# Sheet1.net
KiCad netlist of a schematic drawn in Altium Designer
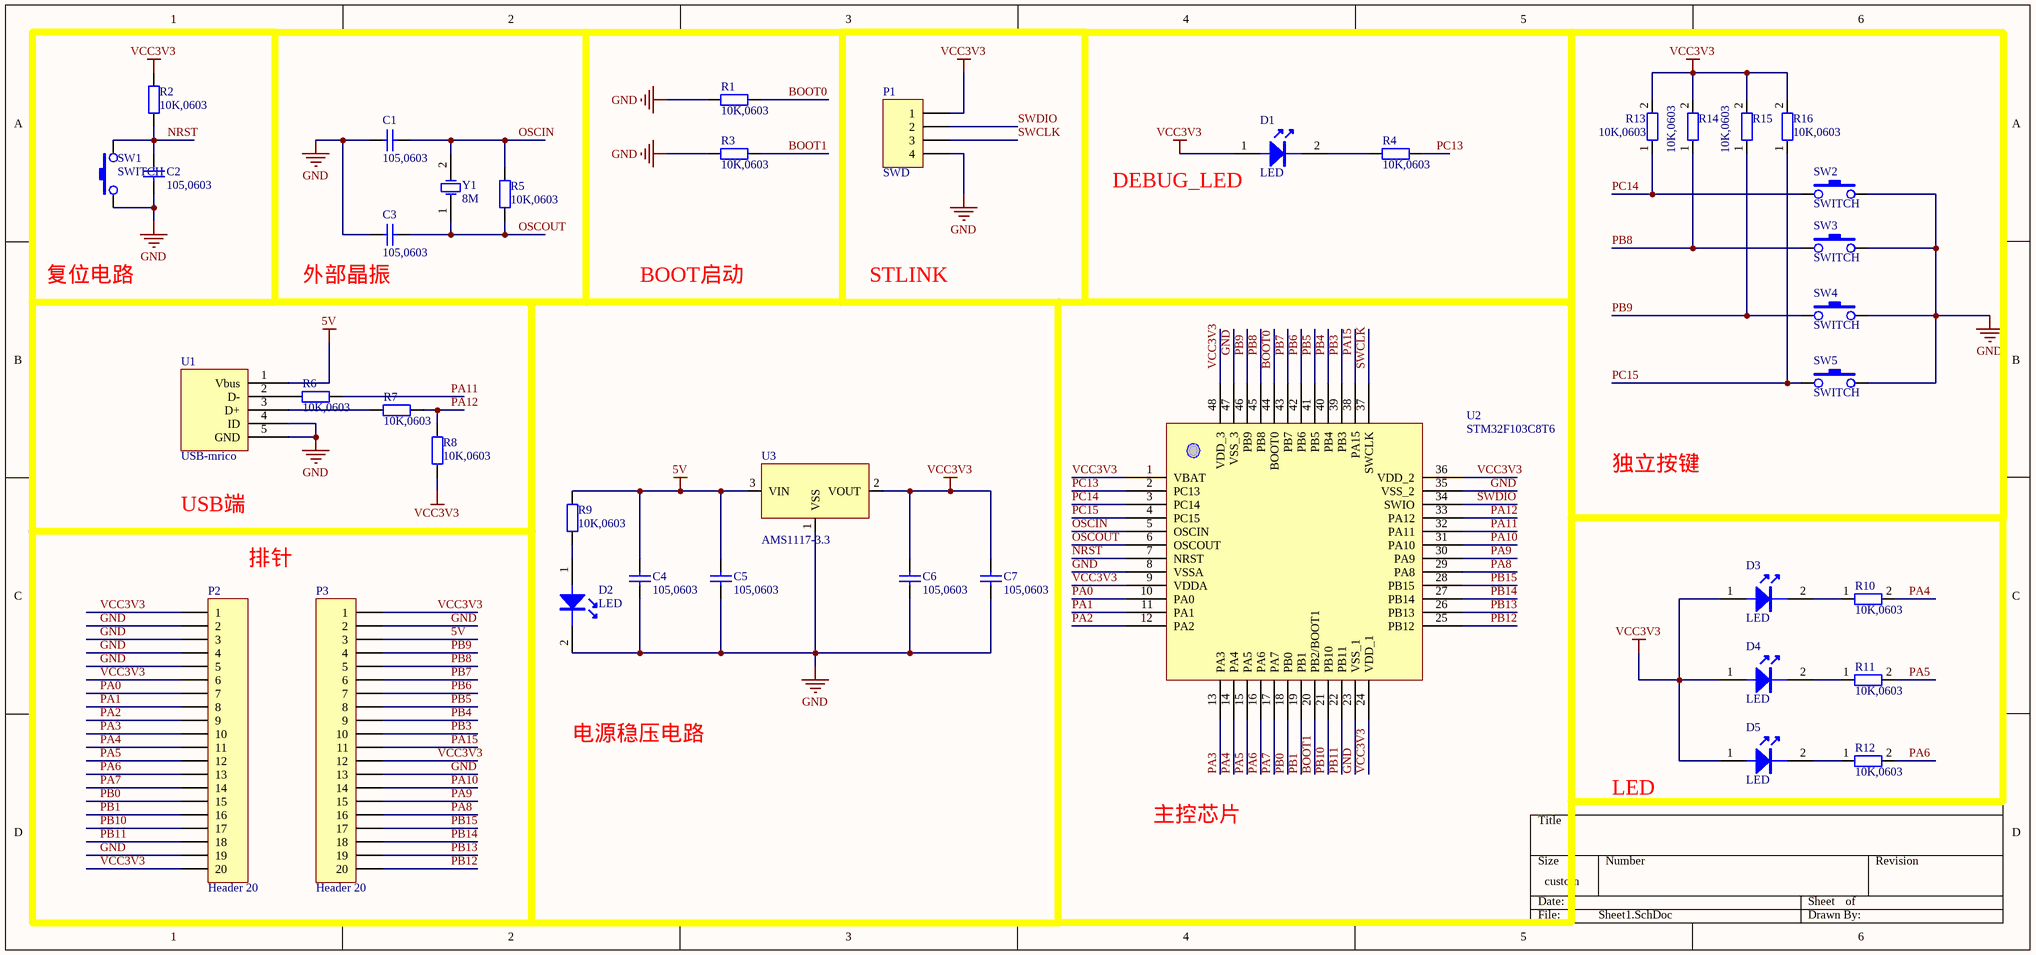
[diagram p0: Sheet1.SchDoc]

(export (version "E")
  (design (tool "Eeschema 10.0.6"))
  (components
    (comp (ref "C1")
      (value "105,0603")
      (footprint "CAP 0603")
      (description "Capacitor")
      (fields (field (name "PUBLISHER") "Altium Limited"))
      (libsource (lib "Schlib1") (part "Cap"))
    )
    (comp (ref "C2")
      (value "105,0603")
      (footprint "CAP 0603")
      (description "Capacitor")
      (fields (field (name "PUBLISHER") "Altium Limited"))
      (libsource (lib "Schlib1") (part "Cap"))
    )
    (comp (ref "C3")
      (value "105,0603")
      (footprint "CAP 0603")
      (description "Capacitor")
      (fields (field (name "PUBLISHER") "Altium Limited"))
      (libsource (lib "Schlib1") (part "Cap"))
    )
    (comp (ref "C4")
      (value "105,0603")
      (footprint "CAP 0603")
      (description "Capacitor")
      (fields (field (name "PUBLISHER") "Altium Limited"))
      (libsource (lib "Schlib1") (part "Cap"))
    )
    (comp (ref "C5")
      (value "105,0603")
      (footprint "CAP 0603")
      (description "Capacitor")
      (fields (field (name "PUBLISHER") "Altium Limited"))
      (libsource (lib "Schlib1") (part "Cap"))
    )
    (comp (ref "C6")
      (value "105,0603")
      (footprint "CAP 0603")
      (description "Capacitor")
      (fields (field (name "PUBLISHER") "Altium Limited"))
      (libsource (lib "Schlib1") (part "Cap"))
    )
    (comp (ref "C7")
      (value "105,0603")
      (footprint "CAP 0603")
      (description "Capacitor")
      (fields (field (name "PUBLISHER") "Altium Limited"))
      (libsource (lib "Schlib1") (part "Cap"))
    )
    (comp (ref "D1") (value "LED") (footprint "LED 0603R") (libsource (lib "Schlib1") (part "LED")))
    (comp (ref "D2") (value "LED") (footprint "LED 0603R") (libsource (lib "Schlib1") (part "LED")))
    (comp (ref "D3") (value "LED") (footprint "LED 0603R") (libsource (lib "Schlib1") (part "LED")))
    (comp (ref "D4") (value "LED") (footprint "LED 0603R") (libsource (lib "Schlib1") (part "LED")))
    (comp (ref "D5") (value "LED") (footprint "LED 0603R") (libsource (lib "Schlib1") (part "LED")))
    (comp (ref "P1")
      (value "SWD")
      (footprint "HDR2.54-WI-4P")
      (description "Header, 4-Pin")
      (fields (field (name "PUBLISHER") "Altium Limited"))
      (libsource (lib "Schlib1") (part "Header 4"))
    )
    (comp (ref "P2")
      (value "Header 20")
      (footprint "HDR2.54-LI-20P")
      (description "Header, 20-Pin")
      (fields (field (name "PUBLISHER") "Altium Limited"))
      (libsource (lib "Schlib1") (part "Header 20"))
    )
    (comp (ref "P3")
      (value "Header 20")
      (footprint "HDR2.54-LI-20P")
      (description "Header, 20-Pin")
      (fields (field (name "PUBLISHER") "Altium Limited"))
      (libsource (lib "") (part "Header 20_1"))
    )
    (comp (ref "R1")
      (value "10K,0603")
      (footprint "RES 0603")
      (description "Resistor")
      (fields (field (name "PUBLISHER") "Altium Limited"))
      (libsource (lib "") (part "Res_1"))
    )
    (comp (ref "R2")
      (value "10K,0603")
      (footprint "RES 0603")
      (description "Resistor")
      (fields (field (name "PUBLISHER") "Altium Limited"))
      (libsource (lib "") (part "Res_2"))
    )
    (comp (ref "R3")
      (value "10K,0603")
      (footprint "RES 0603")
      (description "Resistor")
      (fields (field (name "PUBLISHER") "Altium Limited"))
      (libsource (lib "") (part "Res_1"))
    )
    (comp (ref "R4")
      (value "10K,0603")
      (footprint "RES 0603")
      (description "Resistor")
      (fields (field (name "PUBLISHER") "Altium Limited"))
      (libsource (lib "") (part "Res_1"))
    )
    (comp (ref "R5")
      (value "10K,0603")
      (footprint "RES 0603")
      (description "Resistor")
      (fields (field (name "PUBLISHER") "Altium Limited"))
      (libsource (lib "") (part "Res_2"))
    )
    (comp (ref "R6")
      (value "10K,0603")
      (footprint "RES 0603")
      (description "Resistor")
      (fields (field (name "PUBLISHER") "Altium Limited"))
      (libsource (lib "") (part "Res_1"))
    )
    (comp (ref "R7")
      (value "10K,0603")
      (footprint "RES 0603")
      (description "Resistor")
      (fields (field (name "PUBLISHER") "Altium Limited"))
      (libsource (lib "") (part "Res_1"))
    )
    (comp (ref "R8")
      (value "10K,0603")
      (footprint "RES 0603")
      (description "Resistor")
      (fields (field (name "PUBLISHER") "Altium Limited"))
      (libsource (lib "") (part "Res_2"))
    )
    (comp (ref "R9")
      (value "10K,0603")
      (footprint "RES 0603")
      (description "Resistor")
      (fields (field (name "PUBLISHER") "Altium Limited"))
      (libsource (lib "") (part "Res_2"))
    )
    (comp (ref "R10")
      (value "10K,0603")
      (footprint "RES 0603")
      (description "Resistor")
      (fields (field (name "PUBLISHER") "Altium Limited"))
      (libsource (lib "Schlib1") (part "Res"))
    )
    (comp (ref "R11")
      (value "10K,0603")
      (footprint "RES 0603")
      (description "Resistor")
      (fields (field (name "PUBLISHER") "Altium Limited"))
      (libsource (lib "Schlib1") (part "Res"))
    )
    (comp (ref "R12")
      (value "10K,0603")
      (footprint "RES 0603")
      (description "Resistor")
      (fields (field (name "PUBLISHER") "Altium Limited"))
      (libsource (lib "Schlib1") (part "Res"))
    )
    (comp (ref "R13")
      (value "10K,0603")
      (footprint "RES 0603")
      (description "Resistor")
      (fields (field (name "PUBLISHER") "Altium Limited"))
      (libsource (lib "") (part "Res_3"))
    )
    (comp (ref "R14")
      (value "10K,0603")
      (footprint "RES 0603")
      (description "Resistor")
      (fields (field (name "PUBLISHER") "Altium Limited"))
      (libsource (lib "") (part "Res_3"))
    )
    (comp (ref "R15")
      (value "10K,0603")
      (footprint "RES 0603")
      (description "Resistor")
      (fields (field (name "PUBLISHER") "Altium Limited"))
      (libsource (lib "") (part "Res_3"))
    )
    (comp (ref "R16")
      (value "10K,0603")
      (footprint "RES 0603")
      (description "Resistor")
      (fields (field (name "PUBLISHER") "Altium Limited"))
      (libsource (lib "") (part "Res_3"))
    )
    (comp (ref "SW1")
      (value "SWITCH")
      (footprint "TSW SMD-6*6*5")
      (libsource (lib "Schlib1") (part "SWITCH"))
    )
    (comp (ref "SW2")
      (value "SWITCH")
      (footprint "TSW SMD-6*6*5")
      (libsource (lib "Schlib1") (part "SWITCH"))
    )
    (comp (ref "SW3")
      (value "SWITCH")
      (footprint "TSW SMD-6*6*5")
      (libsource (lib "Schlib1") (part "SWITCH"))
    )
    (comp (ref "SW4")
      (value "SWITCH")
      (footprint "TSW SMD-6*6*5")
      (libsource (lib "Schlib1") (part "SWITCH"))
    )
    (comp (ref "SW5")
      (value "SWITCH")
      (footprint "TSW SMD-6*6*5")
      (libsource (lib "Schlib1") (part "SWITCH"))
    )
    (comp (ref "U1")
      (value "USB-mrico")
      (footprint "USB-micro_A")
      (libsource (lib "Schlib1") (part "USB-MICRO"))
    )
    (comp (ref "U2")
      (value "STM32F103C8T6")
      (footprint "LQFP48 7X7_N")
      (libsource (lib "Schlib1") (part "STM32F103C8T6"))
    )
    (comp (ref "U3")
      (value "AMS1117-3.3")
      (footprint "SOT223")
      (description "5V转3.3V")
      (libsource (lib "Schlib1") (part "AMS1117"))
    )
    (comp (ref "Y1")
      (value "8M")
      (footprint "OSC HC-49SMD")
      (description "Crystal Oscillator")
      (fields (field (name "PUBLISHER") "Altium Limited"))
      (libsource (lib "Schlib1") (part "XTAL"))
    )
  )
  (nets
    (net (code "1") (name "/BOOT0") (class "Default")
      (node (ref "R1") (pin "2") (pinfunction "2_2") (pintype "passive"))
      (node (ref "U2") (pin "44") (pinfunction "BOOT0_44") (pintype "passive"))
    )
    (net (code "2") (name "/BOOT1") (class "Default")
      (node (ref "R3") (pin "2") (pinfunction "2_2") (pintype "passive"))
      (node (ref "U2") (pin "20") (pinfunction "PB2/BOOT1_20") (pintype "passive"))
    )
    (net (code "3") (name "/NRST") (class "Default")
      (node (ref "C2") (pin "2") (pinfunction "2_2") (pintype "passive"))
      (node (ref "R2") (pin "1") (pinfunction "1_1") (pintype "passive"))
      (node (ref "SW1") (pin "2") (pinfunction "2_2") (pintype "passive"))
      (node (ref "U2") (pin "7") (pinfunction "NRST_7") (pintype "passive"))
    )
    (net (code "4") (name "/OSCIN") (class "Default")
      (node (ref "C1") (pin "2") (pinfunction "2_2") (pintype "passive"))
      (node (ref "R5") (pin "2") (pinfunction "2_2") (pintype "passive"))
      (node (ref "U2") (pin "5") (pinfunction "OSCIN_5") (pintype "passive"))
      (node (ref "Y1") (pin "2") (pinfunction "OSC2_2") (pintype "passive"))
    )
    (net (code "5") (name "/OSCOUT") (class "Default")
      (node (ref "C3") (pin "2") (pinfunction "2_2") (pintype "passive"))
      (node (ref "R5") (pin "1") (pinfunction "1_1") (pintype "passive"))
      (node (ref "U2") (pin "6") (pinfunction "OSCOUT_6") (pintype "passive"))
      (node (ref "Y1") (pin "1") (pinfunction "OSC1_1") (pintype "passive"))
    )
    (net (code "6") (name "/PA0") (class "Default")
      (node (ref "P2") (pin "7") (pinfunction "7_7") (pintype "passive"))
      (node (ref "U2") (pin "10") (pinfunction "PA0_10") (pintype "passive"))
    )
    (net (code "7") (name "/PA1") (class "Default")
      (node (ref "P2") (pin "8") (pinfunction "8_8") (pintype "passive"))
      (node (ref "U2") (pin "11") (pinfunction "PA1_11") (pintype "passive"))
    )
    (net (code "8") (name "/PA2") (class "Default")
      (node (ref "P2") (pin "9") (pinfunction "9_9") (pintype "passive"))
      (node (ref "U2") (pin "12") (pinfunction "PA2_12") (pintype "passive"))
    )
    (net (code "9") (name "/PA3") (class "Default")
      (node (ref "P2") (pin "10") (pinfunction "10_10") (pintype "passive"))
      (node (ref "U2") (pin "13") (pinfunction "PA3_13") (pintype "passive"))
    )
    (net (code "10") (name "/PA4") (class "Default")
      (node (ref "P2") (pin "11") (pinfunction "11_11") (pintype "passive"))
      (node (ref "R10") (pin "2") (pinfunction "2_2") (pintype "passive"))
      (node (ref "U2") (pin "14") (pinfunction "PA4_14") (pintype "passive"))
    )
    (net (code "11") (name "/PA5") (class "Default")
      (node (ref "P2") (pin "12") (pinfunction "12_12") (pintype "passive"))
      (node (ref "R11") (pin "2") (pinfunction "2_2") (pintype "passive"))
      (node (ref "U2") (pin "15") (pinfunction "PA5_15") (pintype "passive"))
    )
    (net (code "12") (name "/PA6") (class "Default")
      (node (ref "P2") (pin "13") (pinfunction "13_13") (pintype "passive"))
      (node (ref "R12") (pin "2") (pinfunction "2_2") (pintype "passive"))
      (node (ref "U2") (pin "16") (pinfunction "PA6_16") (pintype "passive"))
    )
    (net (code "13") (name "/PA7") (class "Default")
      (node (ref "P2") (pin "14") (pinfunction "14_14") (pintype "passive"))
      (node (ref "U2") (pin "17") (pinfunction "PA7_17") (pintype "passive"))
    )
    (net (code "14") (name "/PA8") (class "Default")
      (node (ref "P3") (pin "16") (pinfunction "16_16") (pintype "passive"))
      (node (ref "U2") (pin "29") (pinfunction "PA8_29") (pintype "passive"))
    )
    (net (code "15") (name "/PA9") (class "Default")
      (node (ref "P3") (pin "15") (pinfunction "15_15") (pintype "passive"))
      (node (ref "U2") (pin "30") (pinfunction "PA9_30") (pintype "passive"))
    )
    (net (code "16") (name "/PA10") (class "Default")
      (node (ref "P3") (pin "14") (pinfunction "14_14") (pintype "passive"))
      (node (ref "U2") (pin "31") (pinfunction "PA10_31") (pintype "passive"))
    )
    (net (code "17") (name "/PA11") (class "Default")
      (node (ref "R6") (pin "2") (pinfunction "2_2") (pintype "passive"))
      (node (ref "U2") (pin "32") (pinfunction "PA11_32") (pintype "passive"))
    )
    (net (code "18") (name "/PA12") (class "Default")
      (node (ref "R7") (pin "2") (pinfunction "2_2") (pintype "passive"))
      (node (ref "R8") (pin "2") (pinfunction "2_2") (pintype "passive"))
      (node (ref "U2") (pin "33") (pinfunction "PA12_33") (pintype "passive"))
    )
    (net (code "19") (name "/PA15") (class "Default")
      (node (ref "P3") (pin "11") (pinfunction "11_11") (pintype "passive"))
      (node (ref "U2") (pin "38") (pinfunction "PA15_38") (pintype "passive"))
    )
    (net (code "20") (name "/PB0") (class "Default")
      (node (ref "P2") (pin "15") (pinfunction "15_15") (pintype "passive"))
      (node (ref "U2") (pin "18") (pinfunction "PB0_18") (pintype "passive"))
    )
    (net (code "21") (name "/PB1") (class "Default")
      (node (ref "P2") (pin "16") (pinfunction "16_16") (pintype "passive"))
      (node (ref "U2") (pin "19") (pinfunction "PB1_19") (pintype "passive"))
    )
    (net (code "22") (name "/PB3") (class "Default")
      (node (ref "P3") (pin "10") (pinfunction "10_10") (pintype "passive"))
      (node (ref "U2") (pin "39") (pinfunction "PB3_39") (pintype "passive"))
    )
    (net (code "23") (name "/PB4") (class "Default")
      (node (ref "P3") (pin "9") (pinfunction "9_9") (pintype "passive"))
      (node (ref "U2") (pin "40") (pinfunction "PB4_40") (pintype "passive"))
    )
    (net (code "24") (name "/PB5") (class "Default")
      (node (ref "P3") (pin "8") (pinfunction "8_8") (pintype "passive"))
      (node (ref "U2") (pin "41") (pinfunction "PB5_41") (pintype "passive"))
    )
    (net (code "25") (name "/PB6") (class "Default")
      (node (ref "P3") (pin "7") (pinfunction "7_7") (pintype "passive"))
      (node (ref "U2") (pin "42") (pinfunction "PB6_42") (pintype "passive"))
    )
    (net (code "26") (name "/PB7") (class "Default")
      (node (ref "P3") (pin "6") (pinfunction "6_6") (pintype "passive"))
      (node (ref "U2") (pin "43") (pinfunction "PB7_43") (pintype "passive"))
    )
    (net (code "27") (name "/PB8") (class "Default")
      (node (ref "P3") (pin "5") (pinfunction "5_5") (pintype "passive"))
      (node (ref "R14") (pin "1") (pinfunction "1_1") (pintype "passive"))
      (node (ref "SW3") (pin "1") (pinfunction "1_1") (pintype "passive"))
      (node (ref "U2") (pin "45") (pinfunction "PB8_45") (pintype "passive"))
    )
    (net (code "28") (name "/PB9") (class "Default")
      (node (ref "P3") (pin "4") (pinfunction "4_4") (pintype "passive"))
      (node (ref "R15") (pin "1") (pinfunction "1_1") (pintype "passive"))
      (node (ref "SW4") (pin "1") (pinfunction "1_1") (pintype "passive"))
      (node (ref "U2") (pin "46") (pinfunction "PB9_46") (pintype "passive"))
    )
    (net (code "29") (name "/PB10") (class "Default")
      (node (ref "P2") (pin "17") (pinfunction "17_17") (pintype "passive"))
      (node (ref "U2") (pin "21") (pinfunction "PB10_21") (pintype "passive"))
    )
    (net (code "30") (name "/PB11") (class "Default")
      (node (ref "P2") (pin "18") (pinfunction "18_18") (pintype "passive"))
      (node (ref "U2") (pin "22") (pinfunction "PB11_22") (pintype "passive"))
    )
    (net (code "31") (name "/PB12") (class "Default")
      (node (ref "P3") (pin "20") (pinfunction "20_20") (pintype "passive"))
      (node (ref "U2") (pin "25") (pinfunction "PB12_25") (pintype "passive"))
    )
    (net (code "32") (name "/PB13") (class "Default")
      (node (ref "P3") (pin "19") (pinfunction "19_19") (pintype "passive"))
      (node (ref "U2") (pin "26") (pinfunction "PB13_26") (pintype "passive"))
    )
    (net (code "33") (name "/PB14") (class "Default")
      (node (ref "P3") (pin "18") (pinfunction "18_18") (pintype "passive"))
      (node (ref "U2") (pin "27") (pinfunction "PB14_27") (pintype "passive"))
    )
    (net (code "34") (name "/PB15") (class "Default")
      (node (ref "P3") (pin "17") (pinfunction "17_17") (pintype "passive"))
      (node (ref "U2") (pin "28") (pinfunction "PB15_28") (pintype "passive"))
    )
    (net (code "35") (name "/PC13") (class "Default")
      (node (ref "R4") (pin "2") (pinfunction "2_2") (pintype "passive"))
      (node (ref "U2") (pin "2") (pinfunction "PC13_2") (pintype "passive"))
    )
    (net (code "36") (name "/PC14") (class "Default")
      (node (ref "R13") (pin "1") (pinfunction "1_1") (pintype "passive"))
      (node (ref "SW2") (pin "1") (pinfunction "1_1") (pintype "passive"))
      (node (ref "U2") (pin "3") (pinfunction "PC14_3") (pintype "passive"))
    )
    (net (code "37") (name "/PC15") (class "Default")
      (node (ref "R16") (pin "1") (pinfunction "1_1") (pintype "passive"))
      (node (ref "SW5") (pin "1") (pinfunction "1_1") (pintype "passive"))
      (node (ref "U2") (pin "4") (pinfunction "PC15_4") (pintype "passive"))
    )
    (net (code "38") (name "/SWCLK") (class "Default")
      (node (ref "P1") (pin "3") (pinfunction "3_3") (pintype "passive"))
      (node (ref "U2") (pin "37") (pinfunction "SWCLK_37") (pintype "passive"))
    )
    (net (code "39") (name "/SWDIO") (class "Default")
      (node (ref "P1") (pin "2") (pinfunction "2_2") (pintype "passive"))
      (node (ref "U2") (pin "34") (pinfunction "SWIO_34") (pintype "passive"))
    )
    (net (code "40") (name "5V") (class "Default")
      (node (ref "C4") (pin "2") (pinfunction "2_2") (pintype "passive"))
      (node (ref "C5") (pin "2") (pinfunction "2_2") (pintype "passive"))
      (node (ref "P3") (pin "3") (pinfunction "3_3") (pintype "passive"))
      (node (ref "R9") (pin "2") (pinfunction "2_2") (pintype "passive"))
      (node (ref "U1") (pin "1") (pinfunction "Vbus_1") (pintype "passive"))
      (node (ref "U3") (pin "3") (pinfunction "VIN_3") (pintype "passive"))
    )
    (net (code "41") (name "GND") (class "Default")
      (node (ref "C1") (pin "1") (pinfunction "1_1") (pintype "passive"))
      (node (ref "C2") (pin "1") (pinfunction "1_1") (pintype "passive"))
      (node (ref "C3") (pin "1") (pinfunction "1_1") (pintype "passive"))
      (node (ref "C4") (pin "1") (pinfunction "1_1") (pintype "passive"))
      (node (ref "C5") (pin "1") (pinfunction "1_1") (pintype "passive"))
      (node (ref "C6") (pin "1") (pinfunction "1_1") (pintype "passive"))
      (node (ref "C7") (pin "1") (pinfunction "1_1") (pintype "passive"))
      (node (ref "D2") (pin "2") (pinfunction "2_2") (pintype "passive"))
      (node (ref "P1") (pin "4") (pinfunction "4_4") (pintype "passive"))
      (node (ref "P2") (pin "19") (pinfunction "19_19") (pintype "passive"))
      (node (ref "P2") (pin "2") (pinfunction "2_2") (pintype "passive"))
      (node (ref "P2") (pin "3") (pinfunction "3_3") (pintype "passive"))
      (node (ref "P2") (pin "4") (pinfunction "4_4") (pintype "passive"))
      (node (ref "P2") (pin "5") (pinfunction "5_5") (pintype "passive"))
      (node (ref "P3") (pin "13") (pinfunction "13_13") (pintype "passive"))
      (node (ref "P3") (pin "2") (pinfunction "2_2") (pintype "passive"))
      (node (ref "R1") (pin "1") (pinfunction "1_1") (pintype "passive"))
      (node (ref "R3") (pin "1") (pinfunction "1_1") (pintype "passive"))
      (node (ref "SW1") (pin "1") (pinfunction "1_1") (pintype "passive"))
      (node (ref "SW2") (pin "2") (pinfunction "2_2") (pintype "passive"))
      (node (ref "SW3") (pin "2") (pinfunction "2_2") (pintype "passive"))
      (node (ref "SW4") (pin "2") (pinfunction "2_2") (pintype "passive"))
      (node (ref "SW5") (pin "2") (pinfunction "2_2") (pintype "passive"))
      (node (ref "U1") (pin "4") (pinfunction "ID_4") (pintype "passive"))
      (node (ref "U1") (pin "5") (pinfunction "GND_5") (pintype "passive"))
      (node (ref "U2") (pin "23") (pinfunction "VSS_1_23") (pintype "passive"))
      (node (ref "U2") (pin "35") (pinfunction "VSS_2_35") (pintype "passive"))
      (node (ref "U2") (pin "47") (pinfunction "VSS_3_47") (pintype "passive"))
      (node (ref "U2") (pin "8") (pinfunction "VSSA_8") (pintype "passive"))
      (node (ref "U3") (pin "1") (pinfunction "VSS_1") (pintype "passive"))
    )
    (net (code "42") (name "Net-(D1-Pad2)") (class "Default")
      (node (ref "D1") (pin "2") (pinfunction "2_2") (pintype "passive"))
      (node (ref "R4") (pin "1") (pinfunction "1_1") (pintype "passive"))
    )
    (net (code "43") (name "Net-(D2-Pad1)") (class "Default")
      (node (ref "D2") (pin "1") (pinfunction "1_1") (pintype "passive"))
      (node (ref "R9") (pin "1") (pinfunction "1_1") (pintype "passive"))
    )
    (net (code "44") (name "Net-(D3-Pad2)") (class "Default")
      (node (ref "D3") (pin "2") (pinfunction "2_2") (pintype "passive"))
      (node (ref "R10") (pin "1") (pinfunction "1_1") (pintype "passive"))
    )
    (net (code "45") (name "Net-(D4-Pad2)") (class "Default")
      (node (ref "D4") (pin "2") (pinfunction "2_2") (pintype "passive"))
      (node (ref "R11") (pin "1") (pinfunction "1_1") (pintype "passive"))
    )
    (net (code "46") (name "Net-(D5-Pad2)") (class "Default")
      (node (ref "D5") (pin "2") (pinfunction "2_2") (pintype "passive"))
      (node (ref "R12") (pin "1") (pinfunction "1_1") (pintype "passive"))
    )
    (net (code "47") (name "Net-(U1-D+)") (class "Default")
      (node (ref "R7") (pin "1") (pinfunction "1_1") (pintype "passive"))
      (node (ref "U1") (pin "3") (pinfunction "D+_3") (pintype "passive"))
    )
    (net (code "48") (name "Net-(U1-D-)") (class "Default")
      (node (ref "R6") (pin "1") (pinfunction "1_1") (pintype "passive"))
      (node (ref "U1") (pin "2") (pinfunction "D-_2") (pintype "passive"))
    )
    (net (code "49") (name "VCC3V3") (class "Default")
      (node (ref "C6") (pin "2") (pinfunction "2_2") (pintype "passive"))
      (node (ref "C7") (pin "2") (pinfunction "2_2") (pintype "passive"))
      (node (ref "D1") (pin "1") (pinfunction "1_1") (pintype "passive"))
      (node (ref "D3") (pin "1") (pinfunction "1_1") (pintype "passive"))
      (node (ref "D4") (pin "1") (pinfunction "1_1") (pintype "passive"))
      (node (ref "D5") (pin "1") (pinfunction "1_1") (pintype "passive"))
      (node (ref "P1") (pin "1") (pinfunction "1_1") (pintype "passive"))
      (node (ref "P2") (pin "1") (pinfunction "1_1") (pintype "passive"))
      (node (ref "P2") (pin "20") (pinfunction "20_20") (pintype "passive"))
      (node (ref "P2") (pin "6") (pinfunction "6_6") (pintype "passive"))
      (node (ref "P3") (pin "1") (pinfunction "1_1") (pintype "passive"))
      (node (ref "P3") (pin "12") (pinfunction "12_12") (pintype "passive"))
      (node (ref "R13") (pin "2") (pinfunction "2_2") (pintype "passive"))
      (node (ref "R14") (pin "2") (pinfunction "2_2") (pintype "passive"))
      (node (ref "R15") (pin "2") (pinfunction "2_2") (pintype "passive"))
      (node (ref "R16") (pin "2") (pinfunction "2_2") (pintype "passive"))
      (node (ref "R2") (pin "2") (pinfunction "2_2") (pintype "passive"))
      (node (ref "R8") (pin "1") (pinfunction "1_1") (pintype "passive"))
      (node (ref "U2") (pin "1") (pinfunction "VBAT_1") (pintype "passive"))
      (node (ref "U2") (pin "24") (pinfunction "VDD_1_24") (pintype "passive"))
      (node (ref "U2") (pin "36") (pinfunction "VDD_2_36") (pintype "passive"))
      (node (ref "U2") (pin "48") (pinfunction "VDD_3_48") (pintype "passive"))
      (node (ref "U2") (pin "9") (pinfunction "VDDA_9") (pintype "passive"))
      (node (ref "U3") (pin "2") (pinfunction "VOUT_2") (pintype "passive"))
    )
  )
)
